# TrinketBlinkM0M.net
KiCad netlist of a schematic drawn in EAGLE
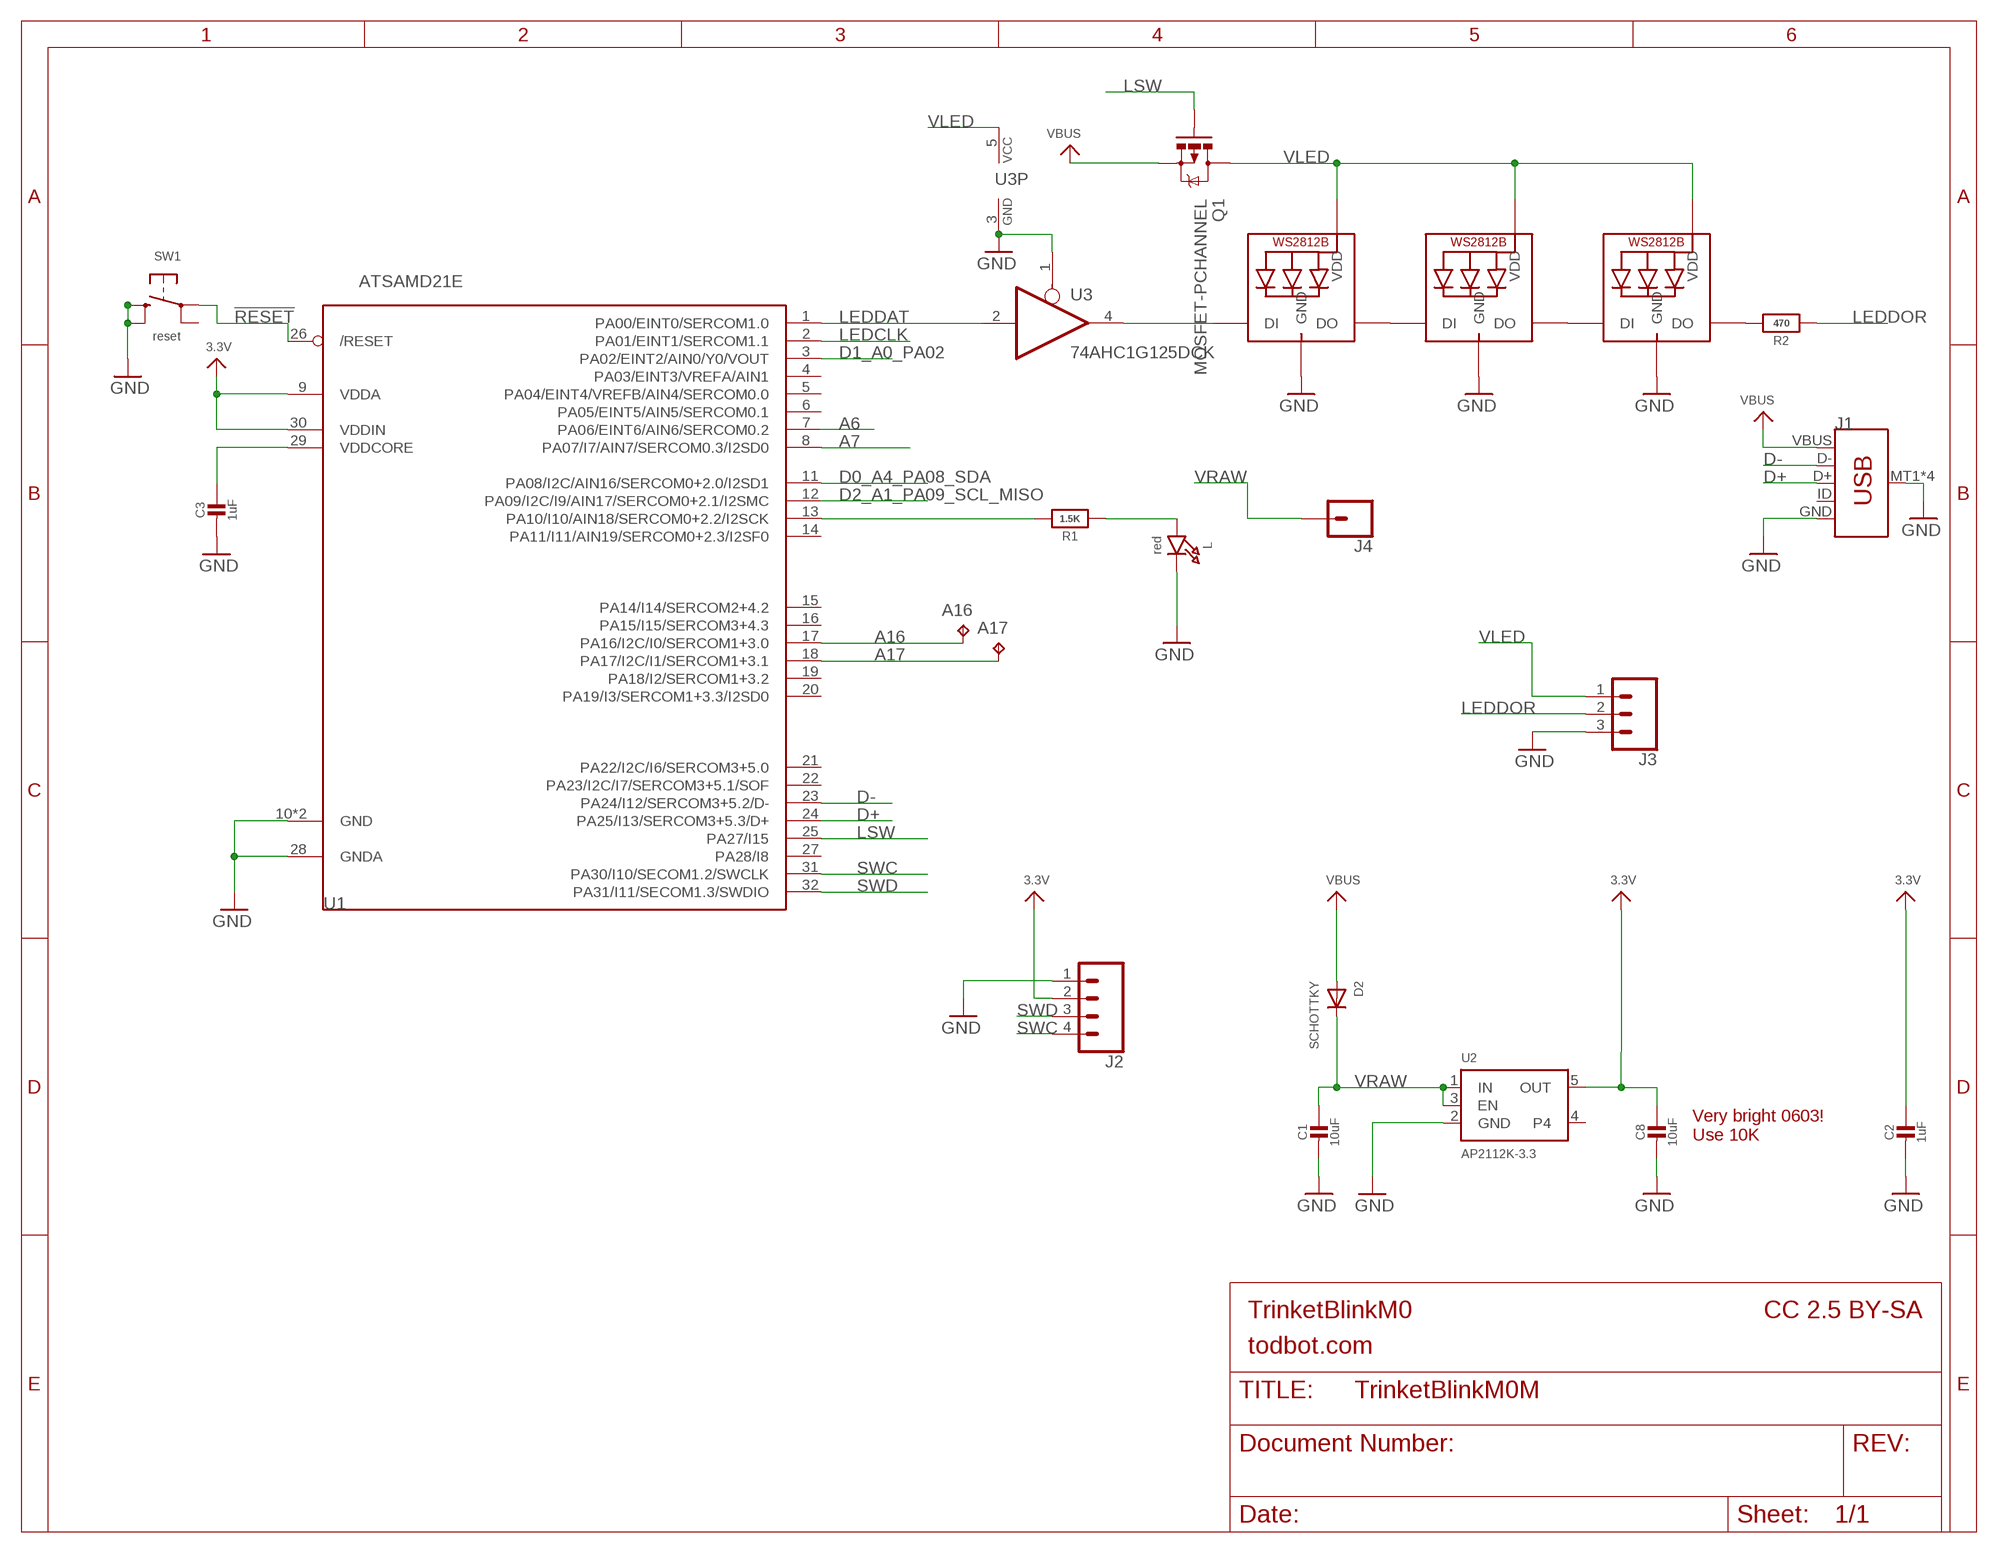
[diagram p0: schematic, sheet 1]

(export (version "E")
  (design (tool "Eeschema 10.0.6"))
  (components
    (comp (ref "A16")
      (value "TPB1,27")
      (footprint "eagle-import:B1,27")
      (libsource (lib "eagle-import") (part "TPB1,27"))
    )
    (comp (ref "A17")
      (value "TPB1,27")
      (footprint "eagle-import:B1,27")
      (libsource (lib "eagle-import") (part "TPB1,27"))
    )
    (comp (ref "C1")
      (value "10uF")
      (footprint "eagle-import:0805-NO")
      (libsource (lib "eagle-import") (part "CAP_CERAMIC0805-NOOUTLINE"))
    )
    (comp (ref "C2")
      (value "1uF")
      (footprint "eagle-import:0603-NO")
      (libsource (lib "eagle-import") (part "CAP_CERAMIC0603_NO"))
    )
    (comp (ref "C3")
      (value "1uF")
      (footprint "eagle-import:0603-NO")
      (libsource (lib "eagle-import") (part "CAP_CERAMIC0603_NO"))
    )
    (comp (ref "C8")
      (value "10uF")
      (footprint "eagle-import:0805-NO")
      (libsource (lib "eagle-import") (part "CAP_CERAMIC0805-NOOUTLINE"))
    )
    (comp (ref "D2")
      (value "SCHOTTKY")
      (footprint "eagle-import:SOD-123FL")
      (libsource (lib "eagle-import") (part "DIODE_SOD-123FL"))
    )
    (comp (ref "J1")
      (value "USB_MICRO-B_SMT")
      (footprint "eagle-import:USB-MICROB")
      (libsource (lib "eagle-import") (part "USB_MICRO-B_SMT"))
    )
    (comp (ref "J2")
      (value "CONN_04")
      (footprint "eagle-import:1X04")
      (libsource (lib "eagle-import") (part "CONN_04"))
    )
    (comp (ref "J3")
      (value "CONN_03")
      (footprint "eagle-import:1X03")
      (libsource (lib "eagle-import") (part "CONN_03"))
    )
    (comp (ref "J4")
      (value "CONN_01")
      (footprint "eagle-import:1X01")
      (libsource (lib "eagle-import") (part "CONN_01"))
    )
    (comp (ref "L")
      (value "red")
      (footprint "eagle-import:CHIPLED_0603_NOOUTLINE")
      (libsource (lib "eagle-import") (part "LED0603_NOOUTLINE"))
    )
    (comp (ref "LED1")
      (value "WS2812B3535")
      (footprint "eagle-import:LED3535")
      (libsource (lib "eagle-import") (part "WS2812B3535"))
    )
    (comp (ref "LED2")
      (value "WS2812B3535")
      (footprint "eagle-import:LED3535")
      (libsource (lib "eagle-import") (part "WS2812B3535"))
    )
    (comp (ref "LED3")
      (value "WS2812B3535")
      (footprint "eagle-import:LED3535")
      (libsource (lib "eagle-import") (part "WS2812B3535"))
    )
    (comp (ref "Q1")
      (value "MOSFET-PCHANNEL")
      (footprint "eagle-import:SOT23-3")
      (libsource (lib "eagle-import") (part "MOSFET-PCHANNEL"))
    )
    (comp (ref "R1")
      (value "1.5K")
      (footprint "eagle-import:0603-NO")
      (libsource (lib "eagle-import") (part "RESISTOR_0603_NOOUT"))
    )
    (comp (ref "R2")
      (value "470")
      (footprint "eagle-import:0603-NO")
      (libsource (lib "eagle-import") (part "RESISTOR_0603_NOOUT"))
    )
    (comp (ref "SW1")
      (value "reset")
      (footprint "eagle-import:BTN_KMR2_4.6X2.8")
      (libsource (lib "eagle-import") (part "SWITCH_TACT_SMT4.6X2.8"))
    )
    (comp (ref "U1")
      (value "ATSAMD21E")
      (footprint "eagle-import:QFN32_5MM")
      (libsource (lib "eagle-import") (part "ATSAMD21E"))
    )
    (comp (ref "U2")
      (value "AP2112K-3.3")
      (footprint "eagle-import:SOT23-5")
      (libsource (lib "eagle-import") (part "VREG_SOT23-5"))
    )
    (comp (ref "U3")
      (value "74AHC1G125DCK")
      (footprint "eagle-import:SC70-5")
      (libsource (lib "eagle-import") (part "741G125DCKAHC"))
    )
  )
  (nets
    (net (code "1") (name "/A6") (class "Default")
      (node (ref "U1") (pin "7") (pinfunction "PA06/EINT6/AIN6/SERCOM0.2_7") (pintype "bidirectional"))
    )
    (net (code "2") (name "/A7") (class "Default")
      (node (ref "U1") (pin "8") (pinfunction "PA07/I7/AIN7/SERCOM0.3/I2SD0_8") (pintype "bidirectional"))
    )
    (net (code "3") (name "/A16") (class "Default")
      (node (ref "A16") (pin "TP") (pinfunction "TP_TP") (pintype "input"))
      (node (ref "U1") (pin "17") (pinfunction "PA16/I2C/I0/SERCOM1+3.0_17") (pintype "bidirectional"))
    )
    (net (code "4") (name "/A17") (class "Default")
      (node (ref "A17") (pin "TP") (pinfunction "TP_TP") (pintype "input"))
      (node (ref "U1") (pin "18") (pinfunction "PA17/I2C/I1/SERCOM1+3.1_18") (pintype "bidirectional"))
    )
    (net (code "5") (name "/D+") (class "Default")
      (node (ref "J1") (pin "D+") (pinfunction "D+_D+") (pintype "bidirectional"))
      (node (ref "U1") (pin "24") (pinfunction "PA25/I13/SERCOM3+5.3/D+_24") (pintype "bidirectional"))
    )
    (net (code "6") (name "/D-") (class "Default")
      (node (ref "J1") (pin "D-") (pinfunction "D-_D-") (pintype "bidirectional"))
      (node (ref "U1") (pin "23") (pinfunction "PA24/I12/SERCOM3+5.2/D-_23") (pintype "bidirectional"))
    )
    (net (code "7") (name "/D0_A4_PA08_SDA") (class "Default")
      (node (ref "U1") (pin "11") (pinfunction "PA08/I2C/AIN16/SERCOM0+2.0/I2SD1_11") (pintype "bidirectional"))
    )
    (net (code "8") (name "/D1_A0_PA02") (class "Default")
      (node (ref "U1") (pin "3") (pinfunction "PA02/EINT2/AIN0/Y0/VOUT_3") (pintype "bidirectional"))
    )
    (net (code "9") (name "/D2_A1_PA09_SCL_MISO") (class "Default")
      (node (ref "U1") (pin "12") (pinfunction "PA09/I2C/I9/AIN17/SERCOM0+2.1/I2SMC_12") (pintype "bidirectional"))
    )
    (net (code "10") (name "/LEDCLK") (class "Default")
      (node (ref "U1") (pin "2") (pinfunction "PA01/EINT1/SERCOM1.1_2") (pintype "bidirectional"))
    )
    (net (code "11") (name "/LEDDAT") (class "Default")
      (node (ref "U1") (pin "1") (pinfunction "PA00/EINT0/SERCOM1.0_1") (pintype "bidirectional"))
      (node (ref "U3") (pin "2") (pinfunction "I_2") (pintype "input"))
    )
    (net (code "12") (name "/LEDDOR") (class "Default")
      (node (ref "J3") (pin "2") (pinfunction "2_2") (pintype "passive"))
      (node (ref "R2") (pin "1") (pinfunction "1_1") (pintype "passive"))
    )
    (net (code "13") (name "/LSW") (class "Default")
      (node (ref "Q1") (pin "1") (pinfunction "G_1") (pintype "passive"))
      (node (ref "U1") (pin "25") (pinfunction "PA27/I15_25") (pintype "bidirectional"))
    )
    (net (code "14") (name "/SWC") (class "Default")
      (node (ref "J2") (pin "4") (pinfunction "4_4") (pintype "passive"))
      (node (ref "U1") (pin "31") (pinfunction "PA30/I10/SECOM1.2/SWCLK_31") (pintype "bidirectional"))
    )
    (net (code "15") (name "/SWD") (class "Default")
      (node (ref "J2") (pin "3") (pinfunction "3_3") (pintype "passive"))
      (node (ref "U1") (pin "32") (pinfunction "PA31/I11/SECOM1.3/SWDIO_32") (pintype "bidirectional"))
    )
    (net (code "16") (name "/VLED") (class "Default")
      (node (ref "J3") (pin "1") (pinfunction "1_1") (pintype "passive"))
      (node (ref "LED1") (pin "2") (pinfunction "VDD_2") (pintype "power_in"))
      (node (ref "LED2") (pin "2") (pinfunction "VDD_2") (pintype "power_in"))
      (node (ref "LED3") (pin "2") (pinfunction "VDD_2") (pintype "power_in"))
      (node (ref "Q1") (pin "3") (pinfunction "D_3") (pintype "passive"))
      (node (ref "U3") (pin "5") (pinfunction "VCC_5") (pintype "power_in"))
    )
    (net (code "17") (name "/VRAW") (class "Default")
      (node (ref "C1") (pin "1") (pinfunction "1_1") (pintype "passive"))
      (node (ref "D2") (pin "C") (pinfunction "C_C") (pintype "passive"))
      (node (ref "J4") (pin "1") (pinfunction "1_1") (pintype "passive"))
      (node (ref "U2") (pin "1") (pinfunction "IN_1") (pintype "power_in"))
      (node (ref "U2") (pin "3") (pinfunction "EN_3") (pintype "input"))
    )
    (net (code "18") (name "/~{RESET}") (class "Default")
      (node (ref "SW1") (pin "A") (pinfunction "P_A") (pintype "passive"))
      (node (ref "U1") (pin "26") (pinfunction "/RESET_26") (pintype "bidirectional"))
    )
    (net (code "19") (name "3.3V") (class "Default")
      (node (ref "C2") (pin "1") (pinfunction "1_1") (pintype "passive"))
      (node (ref "C8") (pin "1") (pinfunction "1_1") (pintype "passive"))
      (node (ref "J2") (pin "2") (pinfunction "2_2") (pintype "passive"))
      (node (ref "U1") (pin "30") (pinfunction "VDDIN_30") (pintype "power_in"))
      (node (ref "U1") (pin "9") (pinfunction "VDDA_9") (pintype "power_in"))
      (node (ref "U2") (pin "5") (pinfunction "OUT_5") (pintype "power_in"))
    )
    (net (code "20") (name "GND") (class "Default")
      (node (ref "C1") (pin "2") (pinfunction "2_2") (pintype "passive"))
      (node (ref "C2") (pin "2") (pinfunction "2_2") (pintype "passive"))
      (node (ref "C3") (pin "2") (pinfunction "2_2") (pintype "passive"))
      (node (ref "C8") (pin "2") (pinfunction "2_2") (pintype "passive"))
      (node (ref "J1") (pin "GND") (pinfunction "GND_GND") (pintype "power_in"))
      (node (ref "J1") (pin "MT1") (pinfunction "SHIELD_MT1") (pintype "bidirectional"))
      (node (ref "J1") (pin "MT2") (pinfunction "SHIELD_MT2") (pintype "bidirectional"))
      (node (ref "J1") (pin "P$1") (pinfunction "SHIELD_P$1") (pintype "bidirectional"))
      (node (ref "J1") (pin "P$2") (pinfunction "SHIELD_P$2") (pintype "bidirectional"))
      (node (ref "J2") (pin "1") (pinfunction "1_1") (pintype "passive"))
      (node (ref "J3") (pin "3") (pinfunction "3_3") (pintype "passive"))
      (node (ref "L") (pin "C") (pinfunction "C_C") (pintype "passive"))
      (node (ref "LED1") (pin "4") (pinfunction "GND_4") (pintype "power_in"))
      (node (ref "LED2") (pin "4") (pinfunction "GND_4") (pintype "power_in"))
      (node (ref "LED3") (pin "4") (pinfunction "GND_4") (pintype "power_in"))
      (node (ref "SW1") (pin "B") (pinfunction "S_B") (pintype "passive"))
      (node (ref "SW1") (pin "B'") (pinfunction "S1_B'") (pintype "passive"))
      (node (ref "U1") (pin "10") (pinfunction "GND_10") (pintype "power_in"))
      (node (ref "U1") (pin "28") (pinfunction "GNDA_28") (pintype "power_in"))
      (node (ref "U1") (pin "33") (pinfunction "GND_33") (pintype "power_in"))
      (node (ref "U2") (pin "2") (pinfunction "GND_2") (pintype "power_in"))
      (node (ref "U3") (pin "1") (pinfunction "OE_1") (pintype "input"))
      (node (ref "U3") (pin "3") (pinfunction "GND_3") (pintype "power_in"))
    )
    (net (code "21") (name "Net-(L-PadA)") (class "Default")
      (node (ref "L") (pin "A") (pinfunction "A_A") (pintype "passive"))
      (node (ref "R1") (pin "1") (pinfunction "1_1") (pintype "passive"))
    )
    (net (code "22") (name "Net-(LED1-DI)") (class "Default")
      (node (ref "LED1") (pin "1") (pinfunction "DI_1") (pintype "input"))
      (node (ref "U3") (pin "4") (pinfunction "O_4") (pintype "tri_state"))
    )
    (net (code "23") (name "Net-(LED1-DO)") (class "Default")
      (node (ref "LED1") (pin "3") (pinfunction "DO_3") (pintype "output"))
      (node (ref "LED2") (pin "1") (pinfunction "DI_1") (pintype "input"))
    )
    (net (code "24") (name "Net-(LED2-DO)") (class "Default")
      (node (ref "LED2") (pin "3") (pinfunction "DO_3") (pintype "output"))
      (node (ref "LED3") (pin "1") (pinfunction "DI_1") (pintype "input"))
    )
    (net (code "25") (name "Net-(LED3-DO)") (class "Default")
      (node (ref "LED3") (pin "3") (pinfunction "DO_3") (pintype "output"))
      (node (ref "R2") (pin "2") (pinfunction "2_2") (pintype "passive"))
    )
    (net (code "26") (name "Net-(U1-PA10{slash}I10{slash}AIN18{slash}SERCOM0+2.2{slash}I2SCK)") (class "Default")
      (node (ref "R1") (pin "2") (pinfunction "2_2") (pintype "passive"))
      (node (ref "U1") (pin "13") (pinfunction "PA10/I10/AIN18/SERCOM0+2.2/I2SCK_13") (pintype "bidirectional"))
    )
    (net (code "27") (name "Net-(U1-VDDCORE)") (class "Default")
      (node (ref "C3") (pin "1") (pinfunction "1_1") (pintype "passive"))
      (node (ref "U1") (pin "29") (pinfunction "VDDCORE_29") (pintype "power_in"))
    )
    (net (code "28") (name "VBUS") (class "Default")
      (node (ref "D2") (pin "A") (pinfunction "A_A") (pintype "passive"))
      (node (ref "J1") (pin "VBUS") (pinfunction "VBUS_VBUS") (pintype "power_in"))
      (node (ref "Q1") (pin "2") (pinfunction "S_2") (pintype "passive"))
    )
    (net (code "29") (name "unconnected-(J1-PadID)") (class "Default")
      (node (ref "J1") (pin "ID") (pinfunction "ID_ID") (pintype "bidirectional"))
    )
    (net (code "30") (name "unconnected-(SW1-P1-PadA')") (class "Default")
      (node (ref "SW1") (pin "A'") (pinfunction "P1_A'") (pintype "passive"))
    )
    (net (code "31") (name "unconnected-(U1-PA03{slash}EINT3{slash}VREFA{slash}AIN1-Pad4)") (class "Default")
      (node (ref "U1") (pin "4") (pinfunction "PA03/EINT3/VREFA/AIN1_4") (pintype "bidirectional"))
    )
    (net (code "32") (name "unconnected-(U1-PA04{slash}EINT4{slash}VREFB{slash}AIN4{slash}SERCOM0.0-Pad5)") (class "Default")
      (node (ref "U1") (pin "5") (pinfunction "PA04/EINT4/VREFB/AIN4/SERCOM0.0_5") (pintype "bidirectional"))
    )
    (net (code "33") (name "unconnected-(U1-PA05{slash}EINT5{slash}AIN5{slash}SERCOM0.1-Pad6)") (class "Default")
      (node (ref "U1") (pin "6") (pinfunction "PA05/EINT5/AIN5/SERCOM0.1_6") (pintype "bidirectional"))
    )
    (net (code "34") (name "unconnected-(U1-PA11{slash}I11{slash}AIN19{slash}SERCOM0+2.3{slash}I2SF0-Pad14)") (class "Default")
      (node (ref "U1") (pin "14") (pinfunction "PA11/I11/AIN19/SERCOM0+2.3/I2SF0_14") (pintype "bidirectional"))
    )
    (net (code "35") (name "unconnected-(U1-PA14{slash}I14{slash}SERCOM2+4.2-Pad15)") (class "Default")
      (node (ref "U1") (pin "15") (pinfunction "PA14/I14/SERCOM2+4.2_15") (pintype "bidirectional"))
    )
    (net (code "36") (name "unconnected-(U1-PA15{slash}I15{slash}SERCOM3+4.3-Pad16)") (class "Default")
      (node (ref "U1") (pin "16") (pinfunction "PA15/I15/SERCOM3+4.3_16") (pintype "bidirectional"))
    )
    (net (code "37") (name "unconnected-(U1-PA18{slash}I2{slash}SERCOM1+3.2-Pad19)") (class "Default")
      (node (ref "U1") (pin "19") (pinfunction "PA18/I2/SERCOM1+3.2_19") (pintype "bidirectional"))
    )
    (net (code "38") (name "unconnected-(U1-PA19{slash}I3{slash}SERCOM1+3.3{slash}I2SD0-Pad20)") (class "Default")
      (node (ref "U1") (pin "20") (pinfunction "PA19/I3/SERCOM1+3.3/I2SD0_20") (pintype "bidirectional"))
    )
    (net (code "39") (name "unconnected-(U1-PA22{slash}I2C{slash}I6{slash}SERCOM3+5.0-Pad21)") (class "Default")
      (node (ref "U1") (pin "21") (pinfunction "PA22/I2C/I6/SERCOM3+5.0_21") (pintype "bidirectional"))
    )
    (net (code "40") (name "unconnected-(U1-PA23{slash}I2C{slash}I7{slash}SERCOM3+5.1{slash}SOF-Pad22)") (class "Default")
      (node (ref "U1") (pin "22") (pinfunction "PA23/I2C/I7/SERCOM3+5.1/SOF_22") (pintype "bidirectional"))
    )
    (net (code "41") (name "unconnected-(U1-PA28{slash}I8-Pad27)") (class "Default")
      (node (ref "U1") (pin "27") (pinfunction "PA28/I8_27") (pintype "bidirectional"))
    )
    (net (code "42") (name "unconnected-(U2-P4-Pad4)") (class "Default")
      (node (ref "U2") (pin "4") (pinfunction "P4_4") (pintype "bidirectional"))
    )
  )
)
